# presTimer.net
KiCad netlist of a schematic drawn in EAGLE
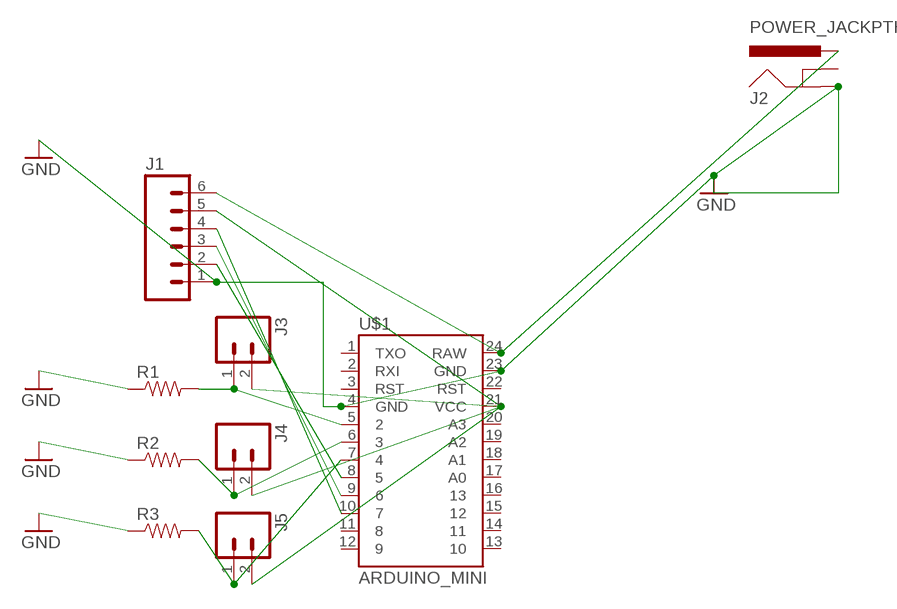
[diagram p0: schematic, sheet 1]

(export (version "E")
  (design (tool "Eeschema 10.0.6"))
  (components
    (comp (ref "J1")
      (value "M06POLAR")
      (footprint "eagle-import:MOLEX-1X6")
      (libsource (lib "eagle-import") (part "M06POLAR"))
    )
    (comp (ref "J2")
      (value "POWER_JACKPTH")
      (footprint "eagle-import:POWER_JACK_PTH")
      (libsource (lib "eagle-import") (part "POWER_JACKPTH"))
    )
    (comp (ref "J3")
      (value "M02LOCK")
      (footprint "eagle-import:1X02_LOCK")
      (libsource (lib "eagle-import") (part "M02LOCK"))
    )
    (comp (ref "J4")
      (value "M02LOCK")
      (footprint "eagle-import:1X02_LOCK")
      (libsource (lib "eagle-import") (part "M02LOCK"))
    )
    (comp (ref "J5")
      (value "M02LOCK")
      (footprint "eagle-import:1X02_LOCK")
      (libsource (lib "eagle-import") (part "M02LOCK"))
    )
    (comp (ref "R1")
      (value "RESISTORAXIAL-0.3")
      (footprint "eagle-import:AXIAL-0.3")
      (libsource (lib "eagle-import") (part "RESISTORAXIAL-0.3"))
    )
    (comp (ref "R2")
      (value "RESISTORAXIAL-0.3")
      (footprint "eagle-import:AXIAL-0.3")
      (libsource (lib "eagle-import") (part "RESISTORAXIAL-0.3"))
    )
    (comp (ref "R3")
      (value "RESISTORAXIAL-0.3")
      (footprint "eagle-import:AXIAL-0.3")
      (libsource (lib "eagle-import") (part "RESISTORAXIAL-0.3"))
    )
    (comp (ref "U$1")
      (value "ARDUINO_MINI")
      (footprint "eagle-import:ARDUINO_MINI")
      (libsource (lib "eagle-import") (part "ARDUINO_MINI"))
    )
  )
  (nets
    (net (code "1") (name "GND") (class "Default")
      (node (ref "J1") (pin "1") (pinfunction "1_1") (pintype "passive"))
      (node (ref "J2") (pin "GND") (pinfunction "GND_GND") (pintype "bidirectional"))
      (node (ref "R1") (pin "P$1") (pinfunction "1_P$1") (pintype "passive"))
      (node (ref "R2") (pin "P$1") (pinfunction "1_P$1") (pintype "passive"))
      (node (ref "R3") (pin "P$1") (pinfunction "1_P$1") (pintype "passive"))
      (node (ref "U$1") (pin "23") (pinfunction "GND_23") (pintype "bidirectional"))
      (node (ref "U$1") (pin "4") (pinfunction "GND_4") (pintype "bidirectional"))
    )
    (net (code "2") (name "Net-(R1-2)") (class "Default")
      (node (ref "J3") (pin "1") (pinfunction "1_1") (pintype "passive"))
      (node (ref "R1") (pin "P$2") (pinfunction "2_P$2") (pintype "passive"))
      (node (ref "U$1") (pin "5") (pinfunction "2_5") (pintype "bidirectional"))
    )
    (net (code "3") (name "Net-(R2-2)") (class "Default")
      (node (ref "J4") (pin "1") (pinfunction "1_1") (pintype "passive"))
      (node (ref "R2") (pin "P$2") (pinfunction "2_P$2") (pintype "passive"))
      (node (ref "U$1") (pin "6") (pinfunction "3_6") (pintype "bidirectional"))
    )
    (net (code "4") (name "Net-(R3-2)") (class "Default")
      (node (ref "J5") (pin "1") (pinfunction "1_1") (pintype "passive"))
      (node (ref "R3") (pin "P$2") (pinfunction "2_P$2") (pintype "passive"))
      (node (ref "U$1") (pin "7") (pinfunction "4_7") (pintype "bidirectional"))
    )
    (net (code "5") (name "Net-(U$1-5)") (class "Default")
      (node (ref "J1") (pin "2") (pinfunction "2_2") (pintype "passive"))
      (node (ref "U$1") (pin "8") (pinfunction "5_8") (pintype "bidirectional"))
    )
    (net (code "6") (name "Net-(U$1-6)") (class "Default")
      (node (ref "J1") (pin "3") (pinfunction "3_3") (pintype "passive"))
      (node (ref "U$1") (pin "9") (pinfunction "6_9") (pintype "bidirectional"))
    )
    (net (code "7") (name "Net-(U$1-7)") (class "Default")
      (node (ref "J1") (pin "4") (pinfunction "4_4") (pintype "passive"))
      (node (ref "U$1") (pin "10") (pinfunction "7_10") (pintype "bidirectional"))
    )
    (net (code "8") (name "Net-(U$1-RAW)") (class "Default")
      (node (ref "J1") (pin "6") (pinfunction "6_6") (pintype "passive"))
      (node (ref "J2") (pin "PWR") (pinfunction "PWR_PWR") (pintype "bidirectional"))
      (node (ref "U$1") (pin "24") (pinfunction "RAW_24") (pintype "bidirectional"))
    )
    (net (code "9") (name "Net-(U$1-VCC)") (class "Default")
      (node (ref "J1") (pin "5") (pinfunction "5_5") (pintype "passive"))
      (node (ref "J3") (pin "2") (pinfunction "2_2") (pintype "passive"))
      (node (ref "J4") (pin "2") (pinfunction "2_2") (pintype "passive"))
      (node (ref "J5") (pin "2") (pinfunction "2_2") (pintype "passive"))
      (node (ref "U$1") (pin "21") (pinfunction "VCC_21") (pintype "bidirectional"))
    )
    (net (code "10") (name "unconnected-(J2-PadGNDBREAK)") (class "Default")
      (node (ref "J2") (pin "GNDBREAK") (pinfunction "GNDBREAK_GNDBREAK") (pintype "bidirectional"))
    )
    (net (code "11") (name "unconnected-(U$1-8-Pad11)") (class "Default")
      (node (ref "U$1") (pin "11") (pinfunction "8_11") (pintype "bidirectional"))
    )
    (net (code "12") (name "unconnected-(U$1-9-Pad12)") (class "Default")
      (node (ref "U$1") (pin "12") (pinfunction "9_12") (pintype "bidirectional"))
    )
    (net (code "13") (name "unconnected-(U$1-10-Pad13)") (class "Default")
      (node (ref "U$1") (pin "13") (pinfunction "10_13") (pintype "bidirectional"))
    )
    (net (code "14") (name "unconnected-(U$1-11-Pad14)") (class "Default")
      (node (ref "U$1") (pin "14") (pinfunction "11_14") (pintype "bidirectional"))
    )
    (net (code "15") (name "unconnected-(U$1-12-Pad15)") (class "Default")
      (node (ref "U$1") (pin "15") (pinfunction "12_15") (pintype "bidirectional"))
    )
    (net (code "16") (name "unconnected-(U$1-13-Pad16)") (class "Default")
      (node (ref "U$1") (pin "16") (pinfunction "13_16") (pintype "bidirectional"))
    )
    (net (code "17") (name "unconnected-(U$1-A0-Pad17)") (class "Default")
      (node (ref "U$1") (pin "17") (pinfunction "A0_17") (pintype "bidirectional"))
    )
    (net (code "18") (name "unconnected-(U$1-A1-Pad18)") (class "Default")
      (node (ref "U$1") (pin "18") (pinfunction "A1_18") (pintype "bidirectional"))
    )
    (net (code "19") (name "unconnected-(U$1-A2-Pad19)") (class "Default")
      (node (ref "U$1") (pin "19") (pinfunction "A2_19") (pintype "bidirectional"))
    )
    (net (code "20") (name "unconnected-(U$1-A3-Pad20)") (class "Default")
      (node (ref "U$1") (pin "20") (pinfunction "A3_20") (pintype "bidirectional"))
    )
    (net (code "21") (name "unconnected-(U$1-RST-Pad3)") (class "Default")
      (node (ref "U$1") (pin "3") (pinfunction "RST_3") (pintype "bidirectional"))
    )
    (net (code "22") (name "unconnected-(U$1-RST-Pad22)") (class "Default")
      (node (ref "U$1") (pin "22") (pinfunction "RST_22") (pintype "bidirectional"))
    )
    (net (code "23") (name "unconnected-(U$1-RXI-Pad2)") (class "Default")
      (node (ref "U$1") (pin "2") (pinfunction "RXI_2") (pintype "bidirectional"))
    )
    (net (code "24") (name "unconnected-(U$1-TXO-Pad1)") (class "Default")
      (node (ref "U$1") (pin "1") (pinfunction "TXO_1") (pintype "bidirectional"))
    )
  )
)
